# cc1101duino.net
KiCad netlist of a schematic drawn in EAGLE
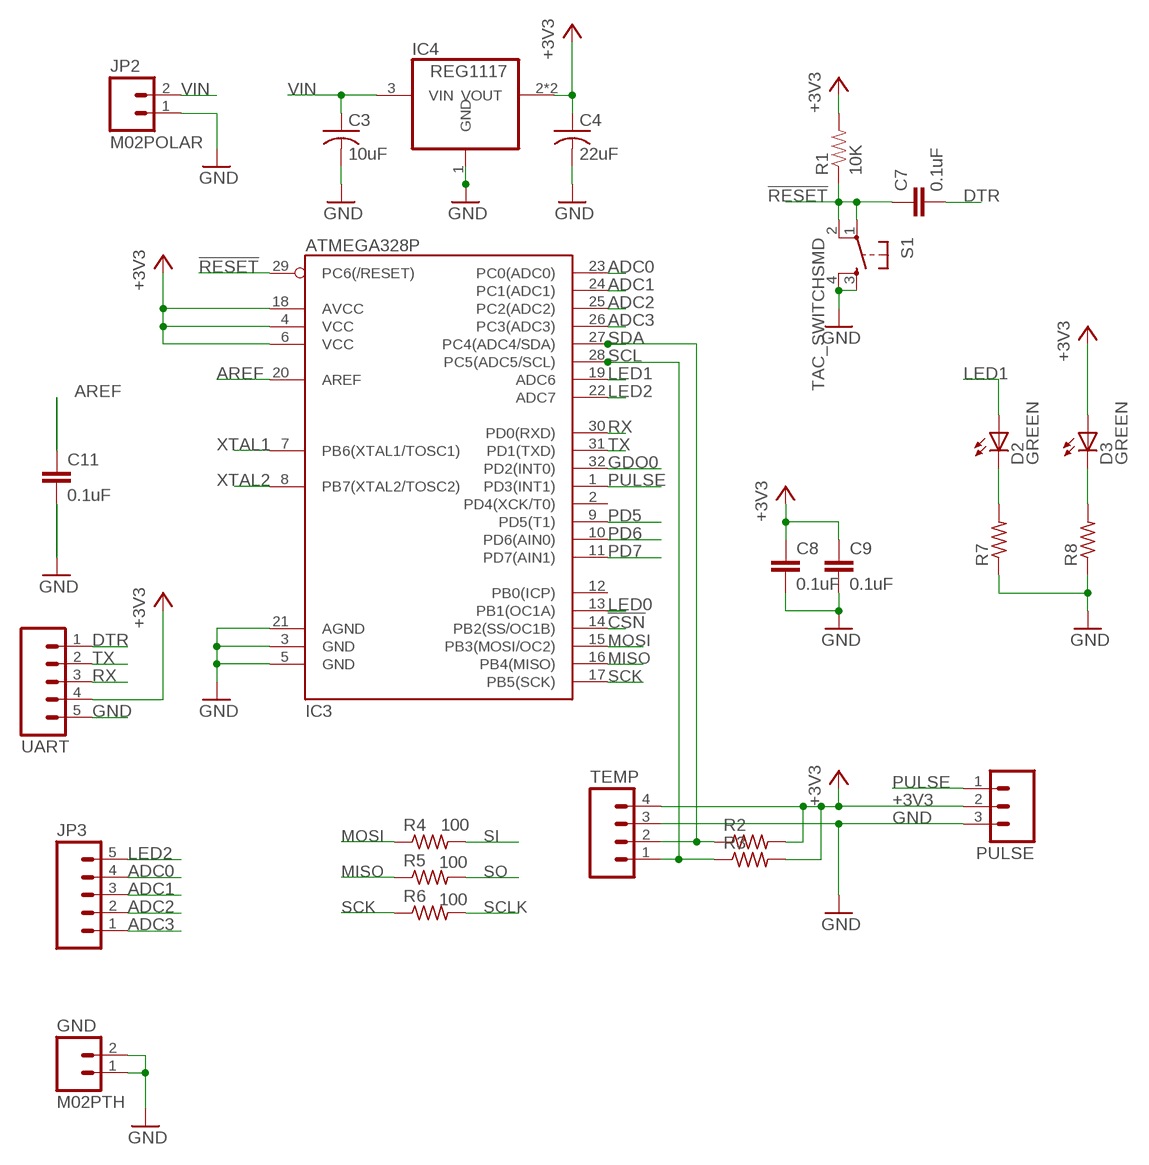
[diagram p0: schematic, sheet 1]
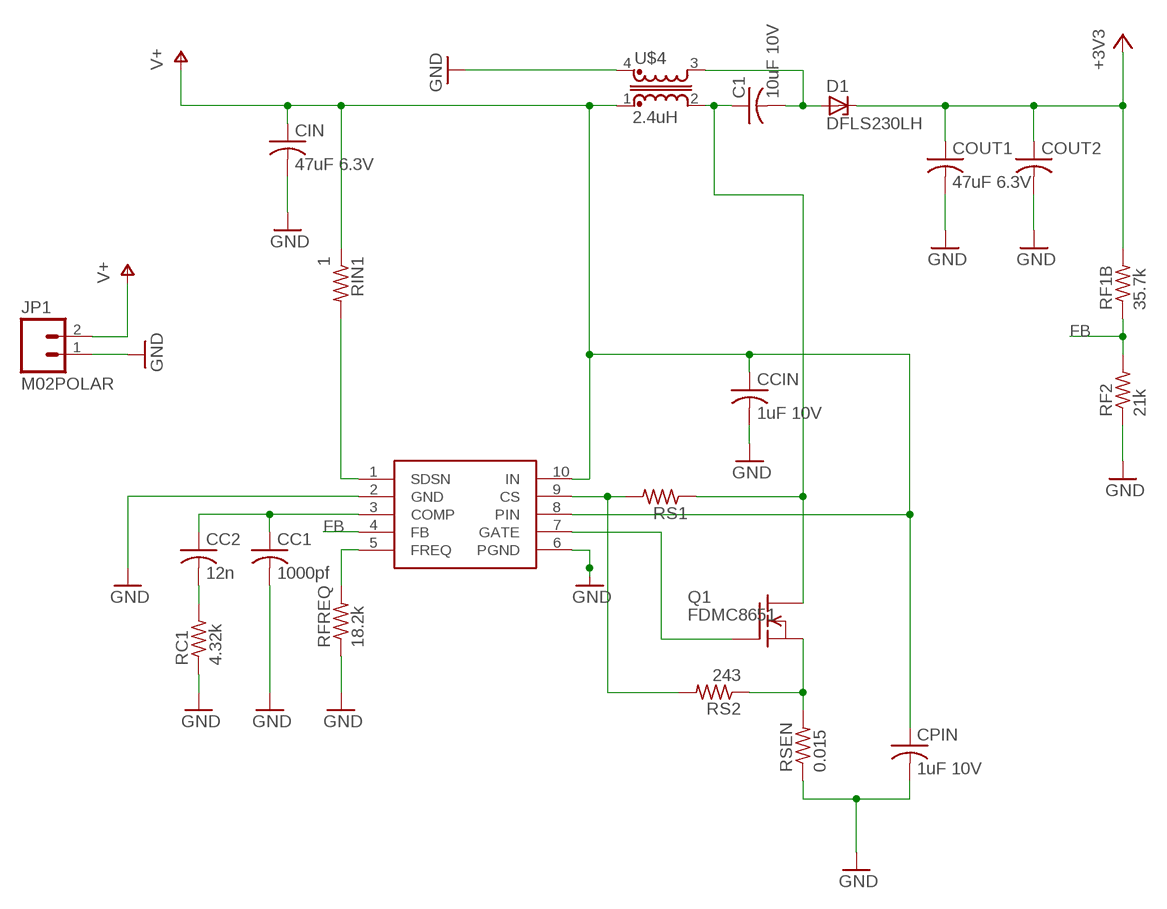
[diagram p1: schematic, sheet 2]
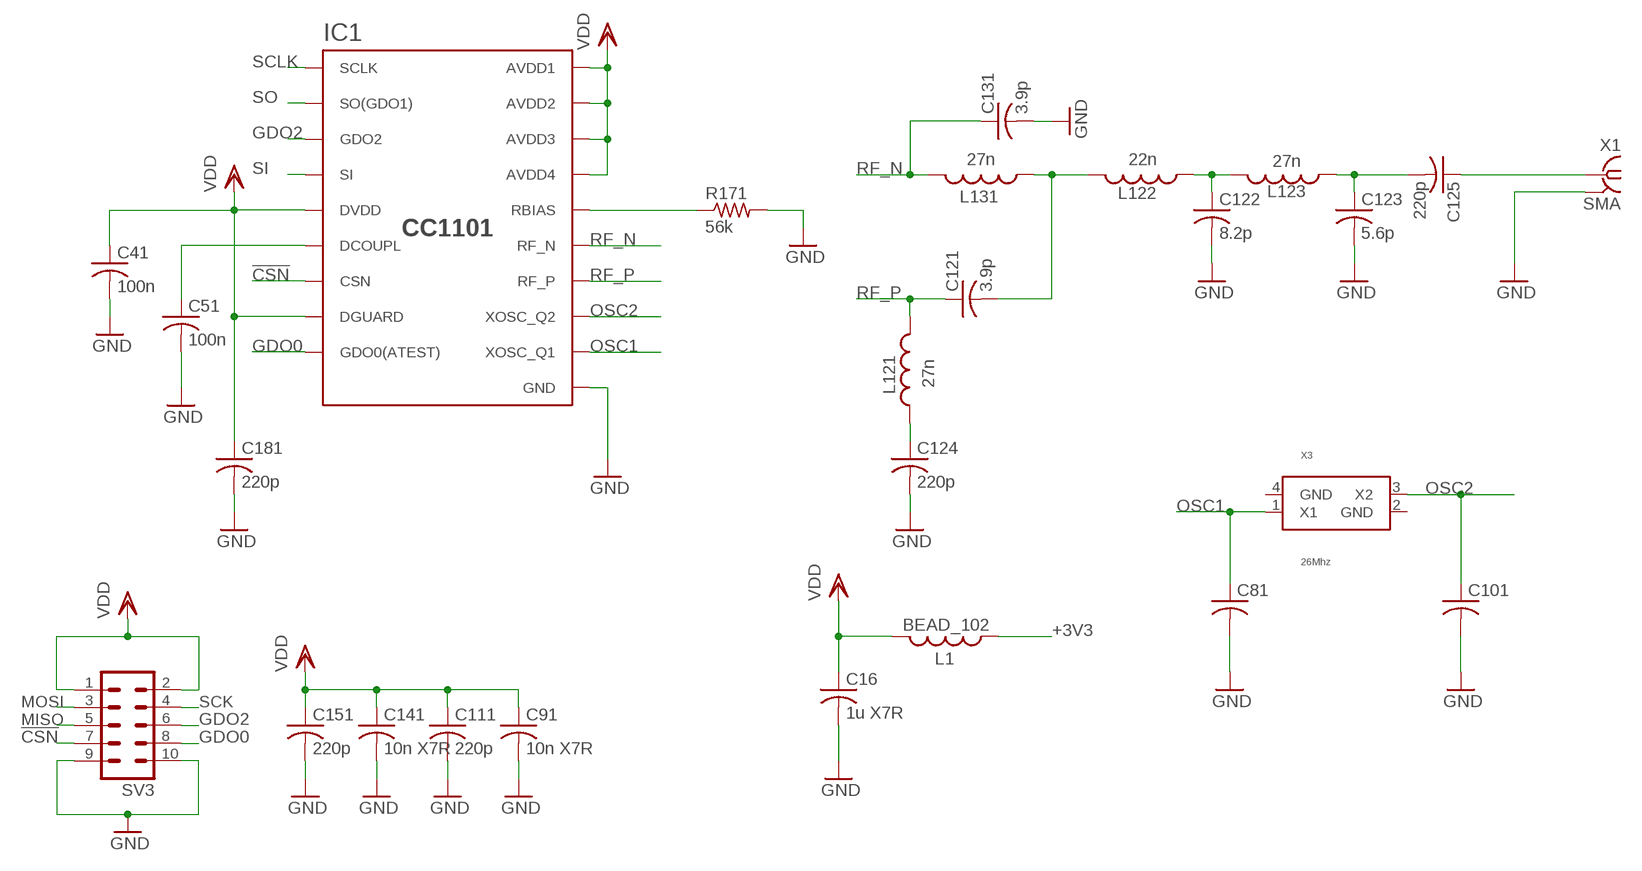
[diagram p2: schematic, sheet 3]

(export (version "E")
  (design (tool "Eeschema 10.0.6"))
  (components
    (comp (ref "C3")
      (value "10uF")
      (footprint "eagle-import:C0805")
      (fields (field (name "MPN") "06034D106MAT2A"))
      (libsource (lib "eagle-import") (part "C-USC0805"))
    )
    (comp (ref "C4")
      (value "22uF")
      (footprint "eagle-import:C0805")
      (fields (field (name "MPN") "06034D106MAT2A"))
      (libsource (lib "eagle-import") (part "C-USC0805"))
    )
    (comp (ref "C7")
      (value "0.1uF")
      (footprint "eagle-import:0805")
      (libsource (lib "eagle-import") (part "CAP0805"))
    )
    (comp (ref "C8")
      (value "0.1uF")
      (footprint "eagle-import:0805")
      (libsource (lib "eagle-import") (part "CAP0805"))
    )
    (comp (ref "C9")
      (value "0.1uF")
      (footprint "eagle-import:0805")
      (libsource (lib "eagle-import") (part "CAP0805"))
    )
    (comp (ref "C11")
      (value "0.1uF")
      (footprint "eagle-import:0805")
      (libsource (lib "eagle-import") (part "CAP0805"))
    )
    (comp (ref "D2")
      (value "GREEN")
      (footprint "eagle-import:LED-0603")
      (libsource (lib "eagle-import") (part "LED-GREEN0603"))
    )
    (comp (ref "D3")
      (value "GREEN")
      (footprint "eagle-import:LED-0603")
      (libsource (lib "eagle-import") (part "LED-GREEN0603"))
    )
    (comp (ref "GND")
      (value "M02PTH")
      (footprint "eagle-import:1X02")
      (libsource (lib "eagle-import") (part "M02PTH"))
    )
    (comp (ref "IC3")
      (value "ATMEGA328P")
      (footprint "eagle-import:TQFP32-08")
      (libsource (lib "eagle-import") (part "ATMEGA328_SMT"))
    )
    (comp (ref "IC4")
      (value "REG1117")
      (footprint "eagle-import:SOT223")
      (libsource (lib "eagle-import") (part "REG1117"))
    )
    (comp (ref "JP2")
      (value "M02POLAR")
      (footprint "eagle-import:MOLEX-1X2")
      (libsource (lib "eagle-import") (part "M02POLAR"))
    )
    (comp (ref "JP3")
      (value "M05PTH")
      (footprint "eagle-import:1X05")
      (libsource (lib "eagle-import") (part "M05PTH"))
    )
    (comp (ref "PULSE")
      (value "M03POLAR")
      (footprint "eagle-import:MOLEX-1X3")
      (libsource (lib "eagle-import") (part "M03POLAR"))
    )
    (comp (ref "R1")
      (value "10K")
      (footprint "eagle-import:0603-RES")
      (libsource (lib "eagle-import") (part "RESISTOR0603-RES"))
    )
    (comp (ref "R2")
      (value "R-US_R0805")
      (footprint "eagle-import:R0805")
      (libsource (lib "eagle-import") (part "resistor_R-US_R0805"))
    )
    (comp (ref "R3")
      (value "R-US_R0805")
      (footprint "eagle-import:R0805")
      (libsource (lib "eagle-import") (part "resistor_R-US_R0805"))
    )
    (comp (ref "R4")
      (value "100")
      (footprint "eagle-import:R0603")
      (libsource (lib "eagle-import") (part "resistor_R-US_R0603"))
    )
    (comp (ref "R5")
      (value "100")
      (footprint "eagle-import:R0603")
      (libsource (lib "eagle-import") (part "resistor_R-US_R0603"))
    )
    (comp (ref "R6")
      (value "100")
      (footprint "eagle-import:R0603")
      (libsource (lib "eagle-import") (part "resistor_R-US_R0603"))
    )
    (comp (ref "R7")
      (value "R-US_R0603")
      (footprint "eagle-import:R0603")
      (libsource (lib "eagle-import") (part "resistor_R-US_R0603"))
    )
    (comp (ref "R8")
      (value "R-US_R0603")
      (footprint "eagle-import:R0603")
      (libsource (lib "eagle-import") (part "resistor_R-US_R0603"))
    )
    (comp (ref "S1")
      (value "TAC_SWITCHSMD")
      (footprint "eagle-import:TACTILE-SWITCH-SMD")
      (libsource (lib "eagle-import") (part "TAC_SWITCHSMD"))
    )
    (comp (ref "TEMP")
      (value "M04POLAR")
      (footprint "eagle-import:MOLEX-1X4")
      (libsource (lib "eagle-import") (part "M04POLAR"))
    )
    (comp (ref "UART")
      (value "M05PTH")
      (footprint "eagle-import:1X05")
      (libsource (lib "eagle-import") (part "M05PTH"))
    )
    (comp (ref "C1")
      (value "10uF 10V")
      (footprint "eagle-import:C0805K")
      (libsource (lib "eagle-import") (part "C-USC0805K"))
    )
    (comp (ref "CC1")
      (value "1000pf")
      (footprint "eagle-import:C0805K")
      (libsource (lib "eagle-import") (part "C-USC0805K"))
    )
    (comp (ref "CC2")
      (value "12n")
      (footprint "eagle-import:C0805K")
      (libsource (lib "eagle-import") (part "C-USC0805K"))
    )
    (comp (ref "CCIN")
      (value "1uF 10V")
      (footprint "eagle-import:C0603K")
      (libsource (lib "eagle-import") (part "C-USC0603K"))
    )
    (comp (ref "CIN")
      (value "47uF 6.3V")
      (footprint "eagle-import:C0805K")
      (libsource (lib "eagle-import") (part "C-USC0805K"))
    )
    (comp (ref "COUT1")
      (value "47uF 6.3V")
      (footprint "eagle-import:C0805K")
      (libsource (lib "eagle-import") (part "C-USC0805K"))
    )
    (comp (ref "COUT2")
      (value "C-USC0805K")
      (footprint "eagle-import:C0805K")
      (libsource (lib "eagle-import") (part "C-USC0805K"))
    )
    (comp (ref "CPIN")
      (value "1uF 10V")
      (footprint "eagle-import:C0603K")
      (libsource (lib "eagle-import") (part "C-USC0603K"))
    )
    (comp (ref "D1")
      (value "DFLS230LH")
      (footprint "eagle-import:DI123")
      (libsource (lib "eagle-import") (part "DFLS230LH"))
    )
    (comp (ref "JP1")
      (value "M02POLAR")
      (footprint "eagle-import:MOLEX-1X2")
      (libsource (lib "eagle-import") (part "M02POLAR"))
    )
    (comp (ref "Q1")
      (value "FDMC8651")
      (footprint "eagle-import:PP8-3X3")
      (libsource (lib "eagle-import") (part "FDMC8651"))
    )
    (comp (ref "RC1")
      (value "4.32k")
      (footprint "eagle-import:R0805")
      (libsource (lib "eagle-import") (part "R-US_R0805"))
    )
    (comp (ref "RF1B")
      (value "35.7k")
      (footprint "eagle-import:R0805")
      (libsource (lib "eagle-import") (part "R-US_R0805"))
    )
    (comp (ref "RF2")
      (value "21k")
      (footprint "eagle-import:R0805")
      (libsource (lib "eagle-import") (part "R-US_R0805"))
    )
    (comp (ref "RFREQ")
      (value "18.2k")
      (footprint "eagle-import:R0805")
      (libsource (lib "eagle-import") (part "R-US_R0805"))
    )
    (comp (ref "RIN1")
      (value "1")
      (footprint "eagle-import:R0805")
      (libsource (lib "eagle-import") (part "R-US_R0805"))
    )
    (comp (ref "RS1")
      (value "R-US_R0805")
      (footprint "eagle-import:R0805")
      (libsource (lib "eagle-import") (part "R-US_R0805"))
    )
    (comp (ref "RS2")
      (value "243")
      (footprint "eagle-import:R0805")
      (libsource (lib "eagle-import") (part "R-US_R0805"))
    )
    (comp (ref "RSEN")
      (value "0.015")
      (footprint "eagle-import:R0805")
      (libsource (lib "eagle-import") (part "R-US_R0805"))
    )
    (comp (ref "U$1")
      (value "ADP1621")
      (footprint "eagle-import:MSOP10")
      (libsource (lib "eagle-import") (part "ADP1621"))
    )
    (comp (ref "U$4")
      (value "2.4uH")
      (footprint "eagle-import:INDUCTOR")
      (libsource (lib "eagle-import") (part "P0175NL"))
    )
    (comp (ref "C16")
      (value "1u X7R")
      (footprint "eagle-import:C0805")
      (libsource (lib "eagle-import") (part "C-USC0805"))
    )
    (comp (ref "C41")
      (value "100n")
      (footprint "eagle-import:C0402")
      (libsource (lib "eagle-import") (part "C-USC0402"))
    )
    (comp (ref "C51")
      (value "100n")
      (footprint "eagle-import:C0402")
      (libsource (lib "eagle-import") (part "C-USC0402"))
    )
    (comp (ref "C81")
      (value "C-USC0402")
      (footprint "eagle-import:C0402")
      (libsource (lib "eagle-import") (part "C-USC0402"))
    )
    (comp (ref "C91")
      (value "10n X7R")
      (footprint "eagle-import:C0402")
      (libsource (lib "eagle-import") (part "C-USC0402"))
    )
    (comp (ref "C101")
      (value "C-USC0402")
      (footprint "eagle-import:C0402")
      (libsource (lib "eagle-import") (part "C-USC0402"))
    )
    (comp (ref "C111")
      (value "220p")
      (footprint "eagle-import:C0402")
      (libsource (lib "eagle-import") (part "C-USC0402"))
    )
    (comp (ref "C121")
      (value "3.9p")
      (footprint "eagle-import:C0402")
      (libsource (lib "eagle-import") (part "C-USC0402"))
    )
    (comp (ref "C122")
      (value "8.2p")
      (footprint "eagle-import:C0402")
      (libsource (lib "eagle-import") (part "C-USC0402"))
    )
    (comp (ref "C123")
      (value "5.6p")
      (footprint "eagle-import:C0402")
      (libsource (lib "eagle-import") (part "C-USC0402"))
    )
    (comp (ref "C124")
      (value "220p")
      (footprint "eagle-import:C0402")
      (libsource (lib "eagle-import") (part "C-USC0402"))
    )
    (comp (ref "C125")
      (value "220p")
      (footprint "eagle-import:C0402")
      (libsource (lib "eagle-import") (part "C-USC0402"))
    )
    (comp (ref "C131")
      (value "3.9p")
      (footprint "eagle-import:C0402")
      (libsource (lib "eagle-import") (part "C-USC0402"))
    )
    (comp (ref "C141")
      (value "10n X7R")
      (footprint "eagle-import:C0402")
      (libsource (lib "eagle-import") (part "C-USC0402"))
    )
    (comp (ref "C151")
      (value "220p")
      (footprint "eagle-import:C0402")
      (libsource (lib "eagle-import") (part "C-USC0402"))
    )
    (comp (ref "C181")
      (value "220p")
      (footprint "eagle-import:C0402")
      (libsource (lib "eagle-import") (part "C-USC0402"))
    )
    (comp (ref "IC1")
      (value "CC1101")
      (footprint "eagle-import:QLP20")
      (libsource (lib "eagle-import") (part "CC1101"))
    )
    (comp (ref "L1")
      (value "BEAD_102")
      (footprint "eagle-import:C0402")
      (libsource (lib "eagle-import") (part "INDUCTOR0402"))
    )
    (comp (ref "L121")
      (value "27n")
      (footprint "eagle-import:C0402")
      (libsource (lib "eagle-import") (part "INDUCTOR0402"))
    )
    (comp (ref "L122")
      (value "22n")
      (footprint "eagle-import:C0402")
      (libsource (lib "eagle-import") (part "INDUCTOR0402"))
    )
    (comp (ref "L123")
      (value "27n")
      (footprint "eagle-import:C0402")
      (libsource (lib "eagle-import") (part "INDUCTOR0402"))
    )
    (comp (ref "L131")
      (value "27n")
      (footprint "eagle-import:C0402")
      (libsource (lib "eagle-import") (part "INDUCTOR0402"))
    )
    (comp (ref "R171")
      (value "56k")
      (footprint "eagle-import:R0402")
      (libsource (lib "eagle-import") (part "R-US_R0402"))
    )
    (comp (ref "SV3")
      (value "MA05-2")
      (footprint "eagle-import:MA05-2")
      (libsource (lib "eagle-import") (part "MA05-2"))
    )
    (comp (ref "X1")
      (value "SMA")
      (footprint "eagle-import:J502-ND-142-0711-821_826")
      (fields (field (name "MF") "JOHNSON COMPONENTS") (field (name "MPN") "142-0711-821"))
      (libsource (lib "eagle-import") (part "SMA-142-0711-821/826"))
    )
    (comp (ref "X3")
      (value "26Mhz")
      (footprint "eagle-import:ABM8G")
      (libsource (lib "eagle-import") (part "ABM8G"))
    )
  )
  (nets
    (net (code "1") (name "+3V3") (class "Default")
      (node (ref "C4") (pin "1") (pinfunction "1_1") (pintype "passive"))
      (node (ref "C8") (pin "1") (pinfunction "1_1") (pintype "passive"))
      (node (ref "C9") (pin "1") (pinfunction "1_1") (pintype "passive"))
      (node (ref "COUT1") (pin "1") (pinfunction "1_1") (pintype "passive"))
      (node (ref "COUT2") (pin "1") (pinfunction "1_1") (pintype "passive"))
      (node (ref "D1") (pin "C") (pinfunction "C_C") (pintype "passive"))
      (node (ref "D3") (pin "A") (pinfunction "A_A") (pintype "passive"))
      (node (ref "IC3") (pin "18") (pinfunction "AVCC_18") (pintype "bidirectional"))
      (node (ref "IC3") (pin "4") (pinfunction "VCC_4") (pintype "bidirectional"))
      (node (ref "IC3") (pin "6") (pinfunction "VCC_6") (pintype "bidirectional"))
      (node (ref "IC4") (pin "2") (pinfunction "VOUT_2") (pintype "output"))
      (node (ref "IC4") (pin "4") (pinfunction "VOUT_4") (pintype "output"))
      (node (ref "L1") (pin "1") (pinfunction "1_1") (pintype "passive"))
      (node (ref "PULSE") (pin "2") (pinfunction "2_2") (pintype "passive"))
      (node (ref "R1") (pin "2") (pinfunction "2_2") (pintype "passive"))
      (node (ref "R2") (pin "2") (pinfunction "2_2") (pintype "passive"))
      (node (ref "R3") (pin "2") (pinfunction "2_2") (pintype "passive"))
      (node (ref "RF1B") (pin "2") (pinfunction "2_2") (pintype "passive"))
      (node (ref "TEMP") (pin "4") (pinfunction "4_4") (pintype "passive"))
      (node (ref "UART") (pin "4") (pinfunction "4_4") (pintype "passive"))
    )
    (net (code "2") (name "ADC0") (class "Default")
      (node (ref "IC3") (pin "23") (pinfunction "PC0(ADC0)_23") (pintype "bidirectional"))
      (node (ref "JP3") (pin "4") (pinfunction "4_4") (pintype "passive"))
    )
    (net (code "3") (name "ADC1") (class "Default")
      (node (ref "IC3") (pin "24") (pinfunction "PC1(ADC1)_24") (pintype "bidirectional"))
      (node (ref "JP3") (pin "3") (pinfunction "3_3") (pintype "passive"))
    )
    (net (code "4") (name "ADC2") (class "Default")
      (node (ref "IC3") (pin "25") (pinfunction "PC2(ADC2)_25") (pintype "bidirectional"))
      (node (ref "JP3") (pin "2") (pinfunction "2_2") (pintype "passive"))
    )
    (net (code "5") (name "ADC3") (class "Default")
      (node (ref "IC3") (pin "26") (pinfunction "PC3(ADC3)_26") (pintype "bidirectional"))
      (node (ref "JP3") (pin "1") (pinfunction "1_1") (pintype "passive"))
    )
    (net (code "6") (name "AREF") (class "Default")
      (node (ref "C11") (pin "1") (pinfunction "1_1") (pintype "passive"))
      (node (ref "IC3") (pin "20") (pinfunction "AREF_20") (pintype "bidirectional"))
    )
    (net (code "7") (name "DTR") (class "Default")
      (node (ref "C7") (pin "2") (pinfunction "2_2") (pintype "passive"))
      (node (ref "UART") (pin "1") (pinfunction "1_1") (pintype "passive"))
    )
    (net (code "8") (name "FB") (class "Default")
      (node (ref "RF1B") (pin "1") (pinfunction "1_1") (pintype "passive"))
      (node (ref "RF2") (pin "2") (pinfunction "2_2") (pintype "passive"))
      (node (ref "U$1") (pin "4") (pinfunction "FB_4") (pintype "bidirectional"))
    )
    (net (code "9") (name "GDO0") (class "Default")
      (node (ref "IC1") (pin "6") (pinfunction "GDO0(ATEST)_6") (pintype "bidirectional"))
      (node (ref "IC3") (pin "32") (pinfunction "PD2(INT0)_32") (pintype "bidirectional"))
      (node (ref "SV3") (pin "8") (pinfunction "8_8") (pintype "passive"))
    )
    (net (code "10") (name "GDO2") (class "Default")
      (node (ref "IC1") (pin "3") (pinfunction "GDO2_3") (pintype "bidirectional"))
      (node (ref "SV3") (pin "6") (pinfunction "6_6") (pintype "passive"))
    )
    (net (code "11") (name "GND") (class "Default")
      (node (ref "C101") (pin "2") (pinfunction "2_2") (pintype "passive"))
      (node (ref "C11") (pin "2") (pinfunction "2_2") (pintype "passive"))
      (node (ref "C111") (pin "2") (pinfunction "2_2") (pintype "passive"))
      (node (ref "C122") (pin "2") (pinfunction "2_2") (pintype "passive"))
      (node (ref "C123") (pin "2") (pinfunction "2_2") (pintype "passive"))
      (node (ref "C124") (pin "2") (pinfunction "2_2") (pintype "passive"))
      (node (ref "C131") (pin "2") (pinfunction "2_2") (pintype "passive"))
      (node (ref "C141") (pin "2") (pinfunction "2_2") (pintype "passive"))
      (node (ref "C151") (pin "2") (pinfunction "2_2") (pintype "passive"))
      (node (ref "C16") (pin "2") (pinfunction "2_2") (pintype "passive"))
      (node (ref "C181") (pin "2") (pinfunction "2_2") (pintype "passive"))
      (node (ref "C3") (pin "2") (pinfunction "2_2") (pintype "passive"))
      (node (ref "C4") (pin "2") (pinfunction "2_2") (pintype "passive"))
      (node (ref "C41") (pin "2") (pinfunction "2_2") (pintype "passive"))
      (node (ref "C51") (pin "2") (pinfunction "2_2") (pintype "passive"))
      (node (ref "C8") (pin "2") (pinfunction "2_2") (pintype "passive"))
      (node (ref "C81") (pin "2") (pinfunction "2_2") (pintype "passive"))
      (node (ref "C9") (pin "2") (pinfunction "2_2") (pintype "passive"))
      (node (ref "C91") (pin "2") (pinfunction "2_2") (pintype "passive"))
      (node (ref "CC1") (pin "2") (pinfunction "2_2") (pintype "passive"))
      (node (ref "CCIN") (pin "2") (pinfunction "2_2") (pintype "passive"))
      (node (ref "CIN") (pin "2") (pinfunction "2_2") (pintype "passive"))
      (node (ref "COUT1") (pin "2") (pinfunction "2_2") (pintype "passive"))
      (node (ref "COUT2") (pin "2") (pinfunction "2_2") (pintype "passive"))
      (node (ref "CPIN") (pin "2") (pinfunction "2_2") (pintype "passive"))
      (node (ref "GND") (pin "1") (pinfunction "1_1") (pintype "passive"))
      (node (ref "GND") (pin "2") (pinfunction "2_2") (pintype "passive"))
      (node (ref "IC1") (pin "16") (pinfunction "GND_16") (pintype "bidirectional"))
      (node (ref "IC1") (pin "19") (pinfunction "GND_19") (pintype "bidirectional"))
      (node (ref "IC1") (pin "GND") (pinfunction "GND_GND") (pintype "bidirectional"))
      (node (ref "IC1") (pin "GND1") (pinfunction "GND_GND1") (pintype "bidirectional"))
      (node (ref "IC1") (pin "GND2") (pinfunction "GND_GND2") (pintype "bidirectional"))
      (node (ref "IC1") (pin "GND3") (pinfunction "GND_GND3") (pintype "bidirectional"))
      (node (ref "IC1") (pin "GND4") (pinfunction "GND_GND4") (pintype "bidirectional"))
      (node (ref "IC1") (pin "GND5") (pinfunction "GND_GND5") (pintype "bidirectional"))
      (node (ref "IC3") (pin "21") (pinfunction "AGND_21") (pintype "bidirectional"))
      (node (ref "IC3") (pin "3") (pinfunction "GND_3") (pintype "bidirectional"))
      (node (ref "IC3") (pin "5") (pinfunction "GND_5") (pintype "bidirectional"))
      (node (ref "IC4") (pin "1") (pinfunction "GND_1") (pintype "power_in"))
      (node (ref "JP1") (pin "1") (pinfunction "1_1") (pintype "passive"))
      (node (ref "JP2") (pin "1") (pinfunction "1_1") (pintype "passive"))
      (node (ref "PULSE") (pin "3") (pinfunction "3_3") (pintype "passive"))
      (node (ref "R171") (pin "2") (pinfunction "2_2") (pintype "passive"))
      (node (ref "R7") (pin "1") (pinfunction "1_1") (pintype "passive"))
      (node (ref "R8") (pin "1") (pinfunction "1_1") (pintype "passive"))
      (node (ref "RC1") (pin "1") (pinfunction "1_1") (pintype "passive"))
      (node (ref "RF2") (pin "1") (pinfunction "1_1") (pintype "passive"))
      (node (ref "RFREQ") (pin "1") (pinfunction "1_1") (pintype "passive"))
      (node (ref "RSEN") (pin "1") (pinfunction "1_1") (pintype "passive"))
      (node (ref "S1") (pin "3") (pinfunction "3_3") (pintype "passive"))
      (node (ref "S1") (pin "4") (pinfunction "4_4") (pintype "passive"))
      (node (ref "SV3") (pin "10") (pinfunction "10_10") (pintype "passive"))
      (node (ref "SV3") (pin "9") (pinfunction "9_9") (pintype "passive"))
      (node (ref "TEMP") (pin "3") (pinfunction "3_3") (pintype "passive"))
      (node (ref "U$1") (pin "2") (pinfunction "GND_2") (pintype "bidirectional"))
      (node (ref "U$1") (pin "6") (pinfunction "PGND_6") (pintype "bidirectional"))
      (node (ref "U$4") (pin "4") (pinfunction "1_4") (pintype "passive"))
      (node (ref "UART") (pin "5") (pinfunction "5_5") (pintype "passive"))
      (node (ref "X1") (pin "G@1") (pinfunction "2_G@1") (pintype "passive"))
      (node (ref "X1") (pin "G@2") (pinfunction "2_G@2") (pintype "passive"))
      (node (ref "X1") (pin "G@3") (pinfunction "2_G@3") (pintype "passive"))
      (node (ref "X1") (pin "G@4") (pinfunction "2_G@4") (pintype "passive"))
    )
    (net (code "12") (name "LED0") (class "Default")
      (node (ref "IC3") (pin "13") (pinfunction "PB1(OC1A)_13") (pintype "bidirectional"))
    )
    (net (code "13") (name "LED1") (class "Default")
      (node (ref "D2") (pin "A") (pinfunction "A_A") (pintype "passive"))
      (node (ref "IC3") (pin "19") (pinfunction "ADC6_19") (pintype "bidirectional"))
    )
    (net (code "14") (name "LED2") (class "Default")
      (node (ref "IC3") (pin "22") (pinfunction "ADC7_22") (pintype "bidirectional"))
      (node (ref "JP3") (pin "5") (pinfunction "5_5") (pintype "passive"))
    )
    (net (code "15") (name "MISO") (class "Default")
      (node (ref "IC3") (pin "16") (pinfunction "PB4(MISO)_16") (pintype "bidirectional"))
      (node (ref "R5") (pin "1") (pinfunction "1_1") (pintype "passive"))
      (node (ref "SV3") (pin "5") (pinfunction "5_5") (pintype "passive"))
    )
    (net (code "16") (name "MOSI") (class "Default")
      (node (ref "IC3") (pin "15") (pinfunction "PB3(MOSI/OC2)_15") (pintype "bidirectional"))
      (node (ref "R4") (pin "1") (pinfunction "1_1") (pintype "passive"))
      (node (ref "SV3") (pin "3") (pinfunction "3_3") (pintype "passive"))
    )
    (net (code "17") (name "Net-(C121-Pad2)") (class "Default")
      (node (ref "C121") (pin "2") (pinfunction "2_2") (pintype "passive"))
      (node (ref "L122") (pin "2") (pinfunction "2_2") (pintype "passive"))
      (node (ref "L131") (pin "1") (pinfunction "1_1") (pintype "passive"))
    )
    (net (code "18") (name "Net-(C122-Pad1)") (class "Default")
      (node (ref "C122") (pin "1") (pinfunction "1_1") (pintype "passive"))
      (node (ref "L122") (pin "1") (pinfunction "1_1") (pintype "passive"))
      (node (ref "L123") (pin "2") (pinfunction "2_2") (pintype "passive"))
    )
    (net (code "19") (name "Net-(C123-Pad1)") (class "Default")
      (node (ref "C123") (pin "1") (pinfunction "1_1") (pintype "passive"))
      (node (ref "C125") (pin "2") (pinfunction "2_2") (pintype "passive"))
      (node (ref "L123") (pin "1") (pinfunction "1_1") (pintype "passive"))
    )
    (net (code "20") (name "Net-(C124-Pad1)") (class "Default")
      (node (ref "C124") (pin "1") (pinfunction "1_1") (pintype "passive"))
      (node (ref "L121") (pin "1") (pinfunction "1_1") (pintype "passive"))
    )
    (net (code "21") (name "Net-(C125-Pad1)") (class "Default")
      (node (ref "C125") (pin "1") (pinfunction "1_1") (pintype "passive"))
      (node (ref "X1") (pin "1") (pinfunction "1_1") (pintype "passive"))
    )
    (net (code "22") (name "Net-(CC2-Pad2)") (class "Default")
      (node (ref "CC2") (pin "2") (pinfunction "2_2") (pintype "passive"))
      (node (ref "RC1") (pin "2") (pinfunction "2_2") (pintype "passive"))
    )
    (net (code "23") (name "Net-(D2-PadC)") (class "Default")
      (node (ref "D2") (pin "C") (pinfunction "C_C") (pintype "passive"))
      (node (ref "R7") (pin "2") (pinfunction "2_2") (pintype "passive"))
    )
    (net (code "24") (name "Net-(D3-PadC)") (class "Default")
      (node (ref "D3") (pin "C") (pinfunction "C_C") (pintype "passive"))
      (node (ref "R8") (pin "2") (pinfunction "2_2") (pintype "passive"))
    )
    (net (code "25") (name "Net-(IC1-DCOUPL)") (class "Default")
      (node (ref "C51") (pin "1") (pinfunction "1_1") (pintype "passive"))
      (node (ref "IC1") (pin "5") (pinfunction "DCOUPL_5") (pintype "bidirectional"))
    )
    (net (code "26") (name "Net-(IC1-RBIAS)") (class "Default")
      (node (ref "IC1") (pin "17") (pinfunction "RBIAS_17") (pintype "bidirectional"))
      (node (ref "R171") (pin "1") (pinfunction "1_1") (pintype "passive"))
    )
    (net (code "27") (name "Net-(Q1-G)") (class "Default")
      (node (ref "Q1") (pin "4") (pinfunction "G_4") (pintype "passive"))
      (node (ref "U$1") (pin "7") (pinfunction "GATE_7") (pintype "bidirectional"))
    )
    (net (code "28") (name "Net-(Q1-S-Pad1)") (class "Default")
      (node (ref "Q1") (pin "1") (pinfunction "S_1") (pintype "passive"))
      (node (ref "Q1") (pin "2") (pinfunction "S_2") (pintype "passive"))
      (node (ref "Q1") (pin "3") (pinfunction "S_3") (pintype "passive"))
      (node (ref "RS2") (pin "1") (pinfunction "1_1") (pintype "passive"))
      (node (ref "RSEN") (pin "2") (pinfunction "2_2") (pintype "passive"))
    )
    (net (code "29") (name "Net-(U$1-COMP)") (class "Default")
      (node (ref "CC1") (pin "1") (pinfunction "1_1") (pintype "passive"))
      (node (ref "CC2") (pin "1") (pinfunction "1_1") (pintype "passive"))
      (node (ref "U$1") (pin "3") (pinfunction "COMP_3") (pintype "bidirectional"))
    )
    (net (code "30") (name "Net-(U$1-CS)") (class "Default")
      (node (ref "RS1") (pin "2") (pinfunction "2_2") (pintype "passive"))
      (node (ref "RS2") (pin "2") (pinfunction "2_2") (pintype "passive"))
      (node (ref "U$1") (pin "9") (pinfunction "CS_9") (pintype "bidirectional"))
    )
    (net (code "31") (name "Net-(U$1-FREQ)") (class "Default")
      (node (ref "RFREQ") (pin "2") (pinfunction "2_2") (pintype "passive"))
      (node (ref "U$1") (pin "5") (pinfunction "FREQ_5") (pintype "bidirectional"))
    )
    (net (code "32") (name "Net-(U$1-SDSN)") (class "Default")
      (node (ref "RIN1") (pin "2") (pinfunction "2_2") (pintype "passive"))
      (node (ref "U$1") (pin "1") (pinfunction "SDSN_1") (pintype "bidirectional"))
    )
    (net (code "33") (name "Net-(U$4-2)") (class "Default")
      (node (ref "C1") (pin "2") (pinfunction "2_2") (pintype "passive"))
      (node (ref "D1") (pin "A") (pinfunction "A_A") (pintype "passive"))
      (node (ref "U$4") (pin "3") (pinfunction "2_3") (pintype "passive"))
    )
    (net (code "34") (name "Net-(U$4-4)") (class "Default")
      (node (ref "C1") (pin "1") (pinfunction "1_1") (pintype "passive"))
      (node (ref "Q1") (pin "5") (pinfunction "D_5") (pintype "passive"))
      (node (ref "Q1") (pin "6") (pinfunction "D_6") (pintype "passive"))
      (node (ref "Q1") (pin "7") (pinfunction "D_7") (pintype "passive"))
      (node (ref "Q1") (pin "8") (pinfunction "D_8") (pintype "passive"))
      (node (ref "Q1") (pin "9") (pinfunction "D_9") (pintype "passive"))
      (node (ref "RS1") (pin "1") (pinfunction "1_1") (pintype "passive"))
      (node (ref "U$4") (pin "2") (pinfunction "4_2") (pintype "passive"))
    )
    (net (code "35") (name "OSC1") (class "Default")
      (node (ref "C81") (pin "1") (pinfunction "1_1") (pintype "passive"))
      (node (ref "IC1") (pin "8") (pinfunction "XOSC_Q1_8") (pintype "bidirectional"))
      (node (ref "X3") (pin "1") (pinfunction "X1_1") (pintype "bidirectional"))
    )
    (net (code "36") (name "OSC2") (class "Default")
      (node (ref "C101") (pin "1") (pinfunction "1_1") (pintype "passive"))
      (node (ref "IC1") (pin "10") (pinfunction "XOSC_Q2_10") (pintype "bidirectional"))
      (node (ref "X3") (pin "3") (pinfunction "X2_3") (pintype "bidirectional"))
    )
    (net (code "37") (name "PD5") (class "Default")
      (node (ref "IC3") (pin "9") (pinfunction "PD5(T1)_9") (pintype "bidirectional"))
    )
    (net (code "38") (name "PD6") (class "Default")
      (node (ref "IC3") (pin "10") (pinfunction "PD6(AIN0)_10") (pintype "bidirectional"))
    )
    (net (code "39") (name "PD7") (class "Default")
      (node (ref "IC3") (pin "11") (pinfunction "PD7(AIN1)_11") (pintype "bidirectional"))
    )
    (net (code "40") (name "PULSE") (class "Default")
      (node (ref "IC3") (pin "1") (pinfunction "PD3(INT1)_1") (pintype "bidirectional"))
      (node (ref "PULSE") (pin "1") (pinfunction "1_1") (pintype "passive"))
    )
    (net (code "41") (name "RF_N") (class "Default")
      (node (ref "C131") (pin "1") (pinfunction "1_1") (pintype "passive"))
      (node (ref "IC1") (pin "13") (pinfunction "RF_N_13") (pintype "bidirectional"))
      (node (ref "L131") (pin "2") (pinfunction "2_2") (pintype "passive"))
    )
    (net (code "42") (name "RF_P") (class "Default")
      (node (ref "C121") (pin "1") (pinfunction "1_1") (pintype "passive"))
      (node (ref "IC1") (pin "12") (pinfunction "RF_P_12") (pintype "bidirectional"))
      (node (ref "L121") (pin "2") (pinfunction "2_2") (pintype "passive"))
    )
    (net (code "43") (name "RX") (class "Default")
      (node (ref "IC3") (pin "30") (pinfunction "PD0(RXD)_30") (pintype "bidirectional"))
      (node (ref "UART") (pin "3") (pinfunction "3_3") (pintype "passive"))
    )
    (net (code "44") (name "SCK") (class "Default")
      (node (ref "IC3") (pin "17") (pinfunction "PB5(SCK)_17") (pintype "bidirectional"))
      (node (ref "R6") (pin "1") (pinfunction "1_1") (pintype "passive"))
      (node (ref "SV3") (pin "4") (pinfunction "4_4") (pintype "passive"))
    )
    (net (code "45") (name "SCL") (class "Default")
      (node (ref "IC3") (pin "28") (pinfunction "PC5(ADC5/SCL)_28") (pintype "bidirectional"))
      (node (ref "R3") (pin "1") (pinfunction "1_1") (pintype "passive"))
      (node (ref "TEMP") (pin "1") (pinfunction "1_1") (pintype "passive"))
    )
    (net (code "46") (name "SCLK") (class "Default")
      (node (ref "IC1") (pin "1") (pinfunction "SCLK_1") (pintype "bidirectional"))
      (node (ref "R6") (pin "2") (pinfunction "2_2") (pintype "passive"))
    )
    (net (code "47") (name "SDA") (class "Default")
      (node (ref "IC3") (pin "27") (pinfunction "PC4(ADC4/SDA)_27") (pintype "bidirectional"))
      (node (ref "R2") (pin "1") (pinfunction "1_1") (pintype "passive"))
      (node (ref "TEMP") (pin "2") (pinfunction "2_2") (pintype "passive"))
    )
    (net (code "48") (name "SI") (class "Default")
      (node (ref "IC1") (pin "20") (pinfunction "SI_20") (pintype "bidirectional"))
      (node (ref "R4") (pin "2") (pinfunction "2_2") (pintype "passive"))
    )
    (net (code "49") (name "SO") (class "Default")
      (node (ref "IC1") (pin "2") (pinfunction "SO(GDO1)_2") (pintype "bidirectional"))
      (node (ref "R5") (pin "2") (pinfunction "2_2") (pintype "passive"))
    )
    (net (code "50") (name "TX") (class "Default")
      (node (ref "IC3") (pin "31") (pinfunction "PD1(TXD)_31") (pintype "bidirectional"))
      (node (ref "UART") (pin "2") (pinfunction "2_2") (pintype "passive"))
    )
    (net (code "51") (name "V+") (class "Default")
      (node (ref "CCIN") (pin "1") (pinfunction "1_1") (pintype "passive"))
      (node (ref "CIN") (pin "1") (pinfunction "1_1") (pintype "passive"))
      (node (ref "CPIN") (pin "1") (pinfunction "1_1") (pintype "passive"))
      (node (ref "JP1") (pin "2") (pinfunction "2_2") (pintype "passive"))
      (node (ref "RIN1") (pin "1") (pinfunction "1_1") (pintype "passive"))
      (node (ref "U$1") (pin "10") (pinfunction "IN_10") (pintype "bidirectional"))
      (node (ref "U$1") (pin "8") (pinfunction "PIN_8") (pintype "bidirectional"))
      (node (ref "U$4") (pin "1") (pinfunction "3_1") (pintype "passive"))
    )
    (net (code "52") (name "VDD") (class "Default")
      (node (ref "C111") (pin "1") (pinfunction "1_1") (pintype "passive"))
      (node (ref "C141") (pin "1") (pinfunction "1_1") (pintype "passive"))
      (node (ref "C151") (pin "1") (pinfunction "1_1") (pintype "passive"))
      (node (ref "C16") (pin "1") (pinfunction "1_1") (pintype "passive"))
      (node (ref "C181") (pin "1") (pinfunction "1_1") (pintype "passive"))
      (node (ref "C41") (pin "1") (pinfunction "1_1") (pintype "passive"))
      (node (ref "C91") (pin "1") (pinfunction "1_1") (pintype "passive"))
      (node (ref "IC1") (pin "11") (pinfunction "AVDD2_11") (pintype "bidirectional"))
      (node (ref "IC1") (pin "14") (pinfunction "AVDD3_14") (pintype "bidirectional"))
      (node (ref "IC1") (pin "15") (pinfunction "AVDD4_15") (pintype "bidirectional"))
      (node (ref "IC1") (pin "18") (pinfunction "DGUARD_18") (pintype "bidirectional"))
      (node (ref "IC1") (pin "4") (pinfunction "DVDD_4") (pintype "bidirectional"))
      (node (ref "IC1") (pin "9") (pinfunction "AVDD1_9") (pintype "bidirectional"))
      (node (ref "L1") (pin "2") (pinfunction "2_2") (pintype "passive"))
      (node (ref "SV3") (pin "1") (pinfunction "1_1") (pintype "passive"))
      (node (ref "SV3") (pin "2") (pinfunction "2_2") (pintype "passive"))
    )
    (net (code "53") (name "VIN") (class "Default")
      (node (ref "C3") (pin "1") (pinfunction "1_1") (pintype "passive"))
      (node (ref "IC4") (pin "3") (pinfunction "VIN_3") (pintype "input"))
      (node (ref "JP2") (pin "2") (pinfunction "2_2") (pintype "passive"))
    )
    (net (code "54") (name "XTAL1") (class "Default")
      (node (ref "IC3") (pin "7") (pinfunction "PB6(XTAL1/TOSC1)_7") (pintype "bidirectional"))
    )
    (net (code "55") (name "XTAL2") (class "Default")
      (node (ref "IC3") (pin "8") (pinfunction "PB7(XTAL2/TOSC2)_8") (pintype "bidirectional"))
    )
    (net (code "56") (name "unconnected-(IC3-PB0(ICP)-Pad12)") (class "Default")
      (node (ref "IC3") (pin "12") (pinfunction "PB0(ICP)_12") (pintype "bidirectional"))
    )
    (net (code "57") (name "unconnected-(IC3-PD4(XCK{slash}T0)-Pad2)") (class "Default")
      (node (ref "IC3") (pin "2") (pinfunction "PD4(XCK/T0)_2") (pintype "bidirectional"))
    )
    (net (code "58") (name "unconnected-(X3-GND-Pad2)") (class "Default")
      (node (ref "X3") (pin "2") (pinfunction "GND_2") (pintype "bidirectional"))
    )
    (net (code "59") (name "unconnected-(X3-GND-Pad4)") (class "Default")
      (node (ref "X3") (pin "4") (pinfunction "GND_4") (pintype "bidirectional"))
    )
    (net (code "60") (name "~{CSN}") (class "Default")
      (node (ref "IC1") (pin "7") (pinfunction "CSN_7") (pintype "bidirectional"))
      (node (ref "IC3") (pin "14") (pinfunction "PB2(SS/OC1B)_14") (pintype "bidirectional"))
      (node (ref "SV3") (pin "7") (pinfunction "7_7") (pintype "passive"))
    )
    (net (code "61") (name "~{RESET}") (class "Default")
      (node (ref "C7") (pin "1") (pinfunction "1_1") (pintype "passive"))
      (node (ref "IC3") (pin "29") (pinfunction "PC6(/RESET)_29") (pintype "bidirectional"))
      (node (ref "R1") (pin "1") (pinfunction "1_1") (pintype "passive"))
      (node (ref "S1") (pin "1") (pinfunction "1_1") (pintype "passive"))
      (node (ref "S1") (pin "2") (pinfunction "2_2") (pintype "passive"))
    )
  )
)
